# phy1.net
KiCad netlist of a schematic drawn in Altium Designer
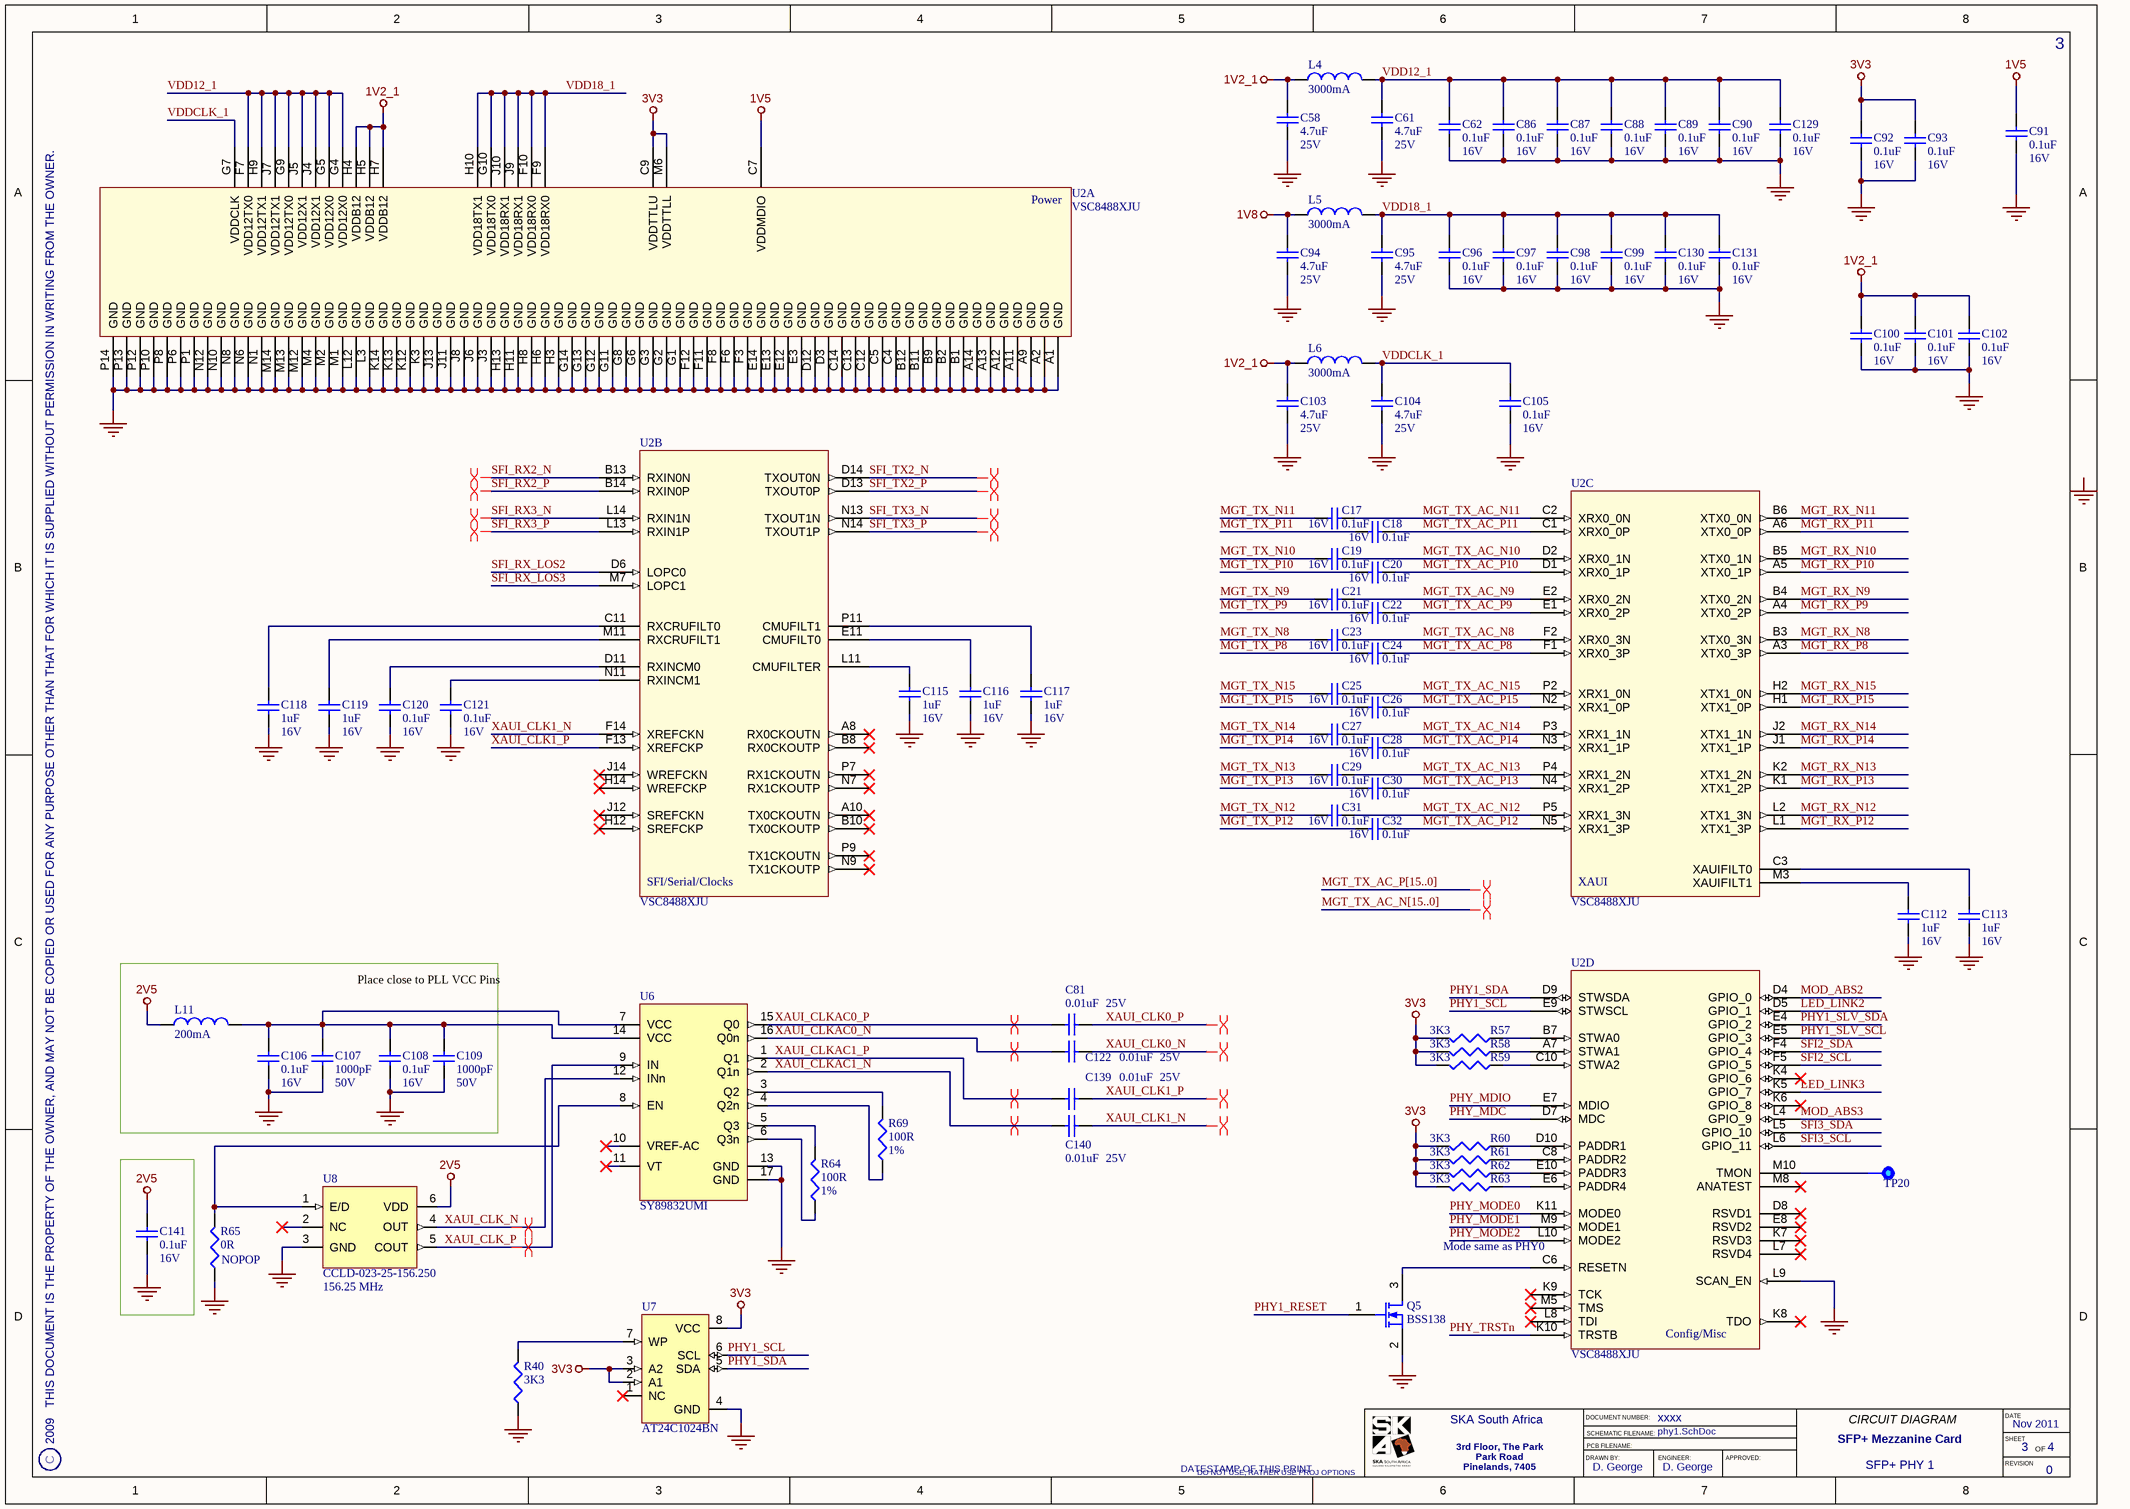
[diagram p0: phy1.SchDoc]

(export (version "E")
  (design (tool "Eeschema 10.0.6"))
  (components
    (comp (ref "C17")
      (value "0.1uF")
      (footprint "CAPC1005X60L")
      (description "0.1uF, Ceramic Capacitor")
      (fields
        (field (name "RATING") "16V")
        (field (name "MANUFACTURER") "VENKEL")
        (field (name "PARTNUM") "C0402X7R160-104KN")
      )
      (libsource (lib "altium_db") (part "CapStd"))
    )
    (comp (ref "C18")
      (value "0.1uF")
      (footprint "CAPC1005X60L")
      (description "0.1uF, Ceramic Capacitor")
      (fields
        (field (name "RATING") "16V")
        (field (name "MANUFACTURER") "VENKEL")
        (field (name "PARTNUM") "C0402X7R160-104KN")
      )
      (libsource (lib "altium_db") (part "CapStd"))
    )
    (comp (ref "C19")
      (value "0.1uF")
      (footprint "CAPC1005X60L")
      (description "0.1uF, Ceramic Capacitor")
      (fields
        (field (name "RATING") "16V")
        (field (name "MANUFACTURER") "VENKEL")
        (field (name "PARTNUM") "C0402X7R160-104KN")
      )
      (libsource (lib "altium_db") (part "CapStd"))
    )
    (comp (ref "C20")
      (value "0.1uF")
      (footprint "CAPC1005X60L")
      (description "0.1uF, Ceramic Capacitor")
      (fields
        (field (name "RATING") "16V")
        (field (name "MANUFACTURER") "VENKEL")
        (field (name "PARTNUM") "C0402X7R160-104KN")
      )
      (libsource (lib "altium_db") (part "CapStd"))
    )
    (comp (ref "C21")
      (value "0.1uF")
      (footprint "CAPC1005X60L")
      (description "0.1uF, Ceramic Capacitor")
      (fields
        (field (name "RATING") "16V")
        (field (name "MANUFACTURER") "VENKEL")
        (field (name "PARTNUM") "C0402X7R160-104KN")
      )
      (libsource (lib "altium_db") (part "CapStd"))
    )
    (comp (ref "C22")
      (value "0.1uF")
      (footprint "CAPC1005X60L")
      (description "0.1uF, Ceramic Capacitor")
      (fields
        (field (name "RATING") "16V")
        (field (name "MANUFACTURER") "VENKEL")
        (field (name "PARTNUM") "C0402X7R160-104KN")
      )
      (libsource (lib "altium_db") (part "CapStd"))
    )
    (comp (ref "C23")
      (value "0.1uF")
      (footprint "CAPC1005X60L")
      (description "0.1uF, Ceramic Capacitor")
      (fields
        (field (name "RATING") "16V")
        (field (name "MANUFACTURER") "VENKEL")
        (field (name "PARTNUM") "C0402X7R160-104KN")
      )
      (libsource (lib "altium_db") (part "CapStd"))
    )
    (comp (ref "C24")
      (value "0.1uF")
      (footprint "CAPC1005X60L")
      (description "0.1uF, Ceramic Capacitor")
      (fields
        (field (name "RATING") "16V")
        (field (name "MANUFACTURER") "VENKEL")
        (field (name "PARTNUM") "C0402X7R160-104KN")
      )
      (libsource (lib "altium_db") (part "CapStd"))
    )
    (comp (ref "C25")
      (value "0.1uF")
      (footprint "CAPC1005X60L")
      (description "0.1uF, Ceramic Capacitor")
      (fields
        (field (name "RATING") "16V")
        (field (name "MANUFACTURER") "VENKEL")
        (field (name "PARTNUM") "C0402X7R160-104KN")
      )
      (libsource (lib "altium_db") (part "CapStd"))
    )
    (comp (ref "C26")
      (value "0.1uF")
      (footprint "CAPC1005X60L")
      (description "0.1uF, Ceramic Capacitor")
      (fields
        (field (name "RATING") "16V")
        (field (name "MANUFACTURER") "VENKEL")
        (field (name "PARTNUM") "C0402X7R160-104KN")
      )
      (libsource (lib "altium_db") (part "CapStd"))
    )
    (comp (ref "C27")
      (value "0.1uF")
      (footprint "CAPC1005X60L")
      (description "0.1uF, Ceramic Capacitor")
      (fields
        (field (name "RATING") "16V")
        (field (name "MANUFACTURER") "VENKEL")
        (field (name "PARTNUM") "C0402X7R160-104KN")
      )
      (libsource (lib "altium_db") (part "CapStd"))
    )
    (comp (ref "C28")
      (value "0.1uF")
      (footprint "CAPC1005X60L")
      (description "0.1uF, Ceramic Capacitor")
      (fields
        (field (name "RATING") "16V")
        (field (name "MANUFACTURER") "VENKEL")
        (field (name "PARTNUM") "C0402X7R160-104KN")
      )
      (libsource (lib "altium_db") (part "CapStd"))
    )
    (comp (ref "C29")
      (value "0.1uF")
      (footprint "CAPC1005X60L")
      (description "0.1uF, Ceramic Capacitor")
      (fields
        (field (name "RATING") "16V")
        (field (name "MANUFACTURER") "VENKEL")
        (field (name "PARTNUM") "C0402X7R160-104KN")
      )
      (libsource (lib "altium_db") (part "CapStd"))
    )
    (comp (ref "C30")
      (value "0.1uF")
      (footprint "CAPC1005X60L")
      (description "0.1uF, Ceramic Capacitor")
      (fields
        (field (name "RATING") "16V")
        (field (name "MANUFACTURER") "VENKEL")
        (field (name "PARTNUM") "C0402X7R160-104KN")
      )
      (libsource (lib "altium_db") (part "CapStd"))
    )
    (comp (ref "C31")
      (value "0.1uF")
      (footprint "CAPC1005X60L")
      (description "0.1uF, Ceramic Capacitor")
      (fields
        (field (name "RATING") "16V")
        (field (name "MANUFACTURER") "VENKEL")
        (field (name "PARTNUM") "C0402X7R160-104KN")
      )
      (libsource (lib "altium_db") (part "CapStd"))
    )
    (comp (ref "C32")
      (value "0.1uF")
      (footprint "CAPC1005X60L")
      (description "0.1uF, Ceramic Capacitor")
      (fields
        (field (name "RATING") "16V")
        (field (name "MANUFACTURER") "VENKEL")
        (field (name "PARTNUM") "C0402X7R160-104KN")
      )
      (libsource (lib "altium_db") (part "CapStd"))
    )
    (comp (ref "C58")
      (value "4.7uF")
      (footprint "CAPC2012X127L")
      (description "4.7uF, Ceramic Capacitor")
      (fields
        (field (name "RATING") "25V")
        (field (name "MANUFACTURER") "MURATA")
        (field (name "PARTNUM") "GRM21BR61E475KA12K")
      )
      (libsource (lib "altium_db") (part "CapStd"))
    )
    (comp (ref "C61")
      (value "4.7uF")
      (footprint "CAPC2012X127L")
      (description "4.7uF, Ceramic Capacitor")
      (fields
        (field (name "RATING") "25V")
        (field (name "MANUFACTURER") "MURATA")
        (field (name "PARTNUM") "GRM21BR61E475KA12K")
      )
      (libsource (lib "altium_db") (part "CapStd"))
    )
    (comp (ref "C62")
      (value "0.1uF")
      (footprint "CAPC1005X60L")
      (description "0.1uF, Ceramic Capacitor")
      (fields
        (field (name "RATING") "16V")
        (field (name "MANUFACTURER") "VENKEL")
        (field (name "PARTNUM") "C0402X7R160-104KN")
      )
      (libsource (lib "altium_db") (part "CapStd"))
    )
    (comp (ref "C81")
      (value "0.01uF")
      (footprint "CAPC1005X55L")
      (description "0.01uF, Ceramic Capacitor")
      (fields
        (field (name "RATING") "25V")
        (field (name "MANUFACTURER") "MURATA")
        (field (name "PARTNUM") "GRM155R71E103KA01D")
      )
      (libsource (lib "altium_db") (part "CapStd"))
    )
    (comp (ref "C86")
      (value "0.1uF")
      (footprint "CAPC1005X60L")
      (description "0.1uF, Ceramic Capacitor")
      (fields
        (field (name "RATING") "16V")
        (field (name "MANUFACTURER") "VENKEL")
        (field (name "PARTNUM") "C0402X7R160-104KN")
      )
      (libsource (lib "altium_db") (part "CapStd"))
    )
    (comp (ref "C87")
      (value "0.1uF")
      (footprint "CAPC1005X60L")
      (description "0.1uF, Ceramic Capacitor")
      (fields
        (field (name "RATING") "16V")
        (field (name "MANUFACTURER") "VENKEL")
        (field (name "PARTNUM") "C0402X7R160-104KN")
      )
      (libsource (lib "altium_db") (part "CapStd"))
    )
    (comp (ref "C88")
      (value "0.1uF")
      (footprint "CAPC1005X60L")
      (description "0.1uF, Ceramic Capacitor")
      (fields
        (field (name "RATING") "16V")
        (field (name "MANUFACTURER") "VENKEL")
        (field (name "PARTNUM") "C0402X7R160-104KN")
      )
      (libsource (lib "altium_db") (part "CapStd"))
    )
    (comp (ref "C89")
      (value "0.1uF")
      (footprint "CAPC1005X60L")
      (description "0.1uF, Ceramic Capacitor")
      (fields
        (field (name "RATING") "16V")
        (field (name "MANUFACTURER") "VENKEL")
        (field (name "PARTNUM") "C0402X7R160-104KN")
      )
      (libsource (lib "altium_db") (part "CapStd"))
    )
    (comp (ref "C90")
      (value "0.1uF")
      (footprint "CAPC1005X60L")
      (description "0.1uF, Ceramic Capacitor")
      (fields
        (field (name "RATING") "16V")
        (field (name "MANUFACTURER") "VENKEL")
        (field (name "PARTNUM") "C0402X7R160-104KN")
      )
      (libsource (lib "altium_db") (part "CapStd"))
    )
    (comp (ref "C91")
      (value "0.1uF")
      (footprint "CAPC1005X60L")
      (description "0.1uF, Ceramic Capacitor")
      (fields
        (field (name "RATING") "16V")
        (field (name "MANUFACTURER") "VENKEL")
        (field (name "PARTNUM") "C0402X7R160-104KN")
      )
      (libsource (lib "altium_db") (part "CapStd"))
    )
    (comp (ref "C92")
      (value "0.1uF")
      (footprint "CAPC1005X60L")
      (description "0.1uF, Ceramic Capacitor")
      (fields
        (field (name "RATING") "16V")
        (field (name "MANUFACTURER") "VENKEL")
        (field (name "PARTNUM") "C0402X7R160-104KN")
      )
      (libsource (lib "altium_db") (part "CapStd"))
    )
    (comp (ref "C93")
      (value "0.1uF")
      (footprint "CAPC1005X60L")
      (description "0.1uF, Ceramic Capacitor")
      (fields
        (field (name "RATING") "16V")
        (field (name "MANUFACTURER") "VENKEL")
        (field (name "PARTNUM") "C0402X7R160-104KN")
      )
      (libsource (lib "altium_db") (part "CapStd"))
    )
    (comp (ref "C94")
      (value "4.7uF")
      (footprint "CAPC2012X127L")
      (description "4.7uF, Ceramic Capacitor")
      (fields
        (field (name "RATING") "25V")
        (field (name "MANUFACTURER") "MURATA")
        (field (name "PARTNUM") "GRM21BR61E475KA12K")
      )
      (libsource (lib "altium_db") (part "CapStd"))
    )
    (comp (ref "C95")
      (value "4.7uF")
      (footprint "CAPC2012X127L")
      (description "4.7uF, Ceramic Capacitor")
      (fields
        (field (name "RATING") "25V")
        (field (name "MANUFACTURER") "MURATA")
        (field (name "PARTNUM") "GRM21BR61E475KA12K")
      )
      (libsource (lib "altium_db") (part "CapStd"))
    )
    (comp (ref "C96")
      (value "0.1uF")
      (footprint "CAPC1005X60L")
      (description "0.1uF, Ceramic Capacitor")
      (fields
        (field (name "RATING") "16V")
        (field (name "MANUFACTURER") "VENKEL")
        (field (name "PARTNUM") "C0402X7R160-104KN")
      )
      (libsource (lib "altium_db") (part "CapStd"))
    )
    (comp (ref "C97")
      (value "0.1uF")
      (footprint "CAPC1005X60L")
      (description "0.1uF, Ceramic Capacitor")
      (fields
        (field (name "RATING") "16V")
        (field (name "MANUFACTURER") "VENKEL")
        (field (name "PARTNUM") "C0402X7R160-104KN")
      )
      (libsource (lib "altium_db") (part "CapStd"))
    )
    (comp (ref "C98")
      (value "0.1uF")
      (footprint "CAPC1005X60L")
      (description "0.1uF, Ceramic Capacitor")
      (fields
        (field (name "RATING") "16V")
        (field (name "MANUFACTURER") "VENKEL")
        (field (name "PARTNUM") "C0402X7R160-104KN")
      )
      (libsource (lib "altium_db") (part "CapStd"))
    )
    (comp (ref "C99")
      (value "0.1uF")
      (footprint "CAPC1005X60L")
      (description "0.1uF, Ceramic Capacitor")
      (fields
        (field (name "RATING") "16V")
        (field (name "MANUFACTURER") "VENKEL")
        (field (name "PARTNUM") "C0402X7R160-104KN")
      )
      (libsource (lib "altium_db") (part "CapStd"))
    )
    (comp (ref "C100")
      (value "0.1uF")
      (footprint "CAPC1005X60L")
      (description "0.1uF, Ceramic Capacitor")
      (fields
        (field (name "RATING") "16V")
        (field (name "MANUFACTURER") "VENKEL")
        (field (name "PARTNUM") "C0402X7R160-104KN")
      )
      (libsource (lib "altium_db") (part "CapStd"))
    )
    (comp (ref "C101")
      (value "0.1uF")
      (footprint "CAPC1005X60L")
      (description "0.1uF, Ceramic Capacitor")
      (fields
        (field (name "RATING") "16V")
        (field (name "MANUFACTURER") "VENKEL")
        (field (name "PARTNUM") "C0402X7R160-104KN")
      )
      (libsource (lib "altium_db") (part "CapStd"))
    )
    (comp (ref "C102")
      (value "0.1uF")
      (footprint "CAPC1005X60L")
      (description "0.1uF, Ceramic Capacitor")
      (fields
        (field (name "RATING") "16V")
        (field (name "MANUFACTURER") "VENKEL")
        (field (name "PARTNUM") "C0402X7R160-104KN")
      )
      (libsource (lib "altium_db") (part "CapStd"))
    )
    (comp (ref "C103")
      (value "4.7uF")
      (footprint "CAPC2012X127L")
      (description "4.7uF, Ceramic Capacitor")
      (fields
        (field (name "RATING") "25V")
        (field (name "MANUFACTURER") "MURATA")
        (field (name "PARTNUM") "GRM21BR61E475KA12K")
      )
      (libsource (lib "altium_db") (part "CapStd"))
    )
    (comp (ref "C104")
      (value "4.7uF")
      (footprint "CAPC2012X127L")
      (description "4.7uF, Ceramic Capacitor")
      (fields
        (field (name "RATING") "25V")
        (field (name "MANUFACTURER") "MURATA")
        (field (name "PARTNUM") "GRM21BR61E475KA12K")
      )
      (libsource (lib "altium_db") (part "CapStd"))
    )
    (comp (ref "C105")
      (value "0.1uF")
      (footprint "CAPC1005X60L")
      (description "0.1uF, Ceramic Capacitor")
      (fields
        (field (name "RATING") "16V")
        (field (name "MANUFACTURER") "VENKEL")
        (field (name "PARTNUM") "C0402X7R160-104KN")
      )
      (libsource (lib "altium_db") (part "CapStd"))
    )
    (comp (ref "C106")
      (value "0.1uF")
      (footprint "CAPC1005X60L")
      (description "0.1uF, Ceramic Capacitor")
      (fields
        (field (name "RATING") "16V")
        (field (name "MANUFACTURER") "VENKEL")
        (field (name "PARTNUM") "C0402X7R160-104KN")
      )
      (libsource (lib "altium_db") (part "CapStd"))
    )
    (comp (ref "C107")
      (value "1000pF")
      (footprint "CAPC1005X55L")
      (description "1000pF, Ceramic Capacitor")
      (fields
        (field (name "RATING") "50V")
        (field (name "MANUFACTURER") "MURATA")
        (field (name "PARTNUM") "GRM155R61H102KA01D")
      )
      (libsource (lib "altium_db") (part "CapStd"))
    )
    (comp (ref "C108")
      (value "0.1uF")
      (footprint "CAPC1005X60L")
      (description "0.1uF, Ceramic Capacitor")
      (fields
        (field (name "RATING") "16V")
        (field (name "MANUFACTURER") "VENKEL")
        (field (name "PARTNUM") "C0402X7R160-104KN")
      )
      (libsource (lib "altium_db") (part "CapStd"))
    )
    (comp (ref "C109")
      (value "1000pF")
      (footprint "CAPC1005X55L")
      (description "1000pF, Ceramic Capacitor")
      (fields
        (field (name "RATING") "50V")
        (field (name "MANUFACTURER") "MURATA")
        (field (name "PARTNUM") "GRM155R61H102KA01D")
      )
      (libsource (lib "altium_db") (part "CapStd"))
    )
    (comp (ref "C112")
      (value "1uF")
      (footprint "CAPC2012X127L")
      (description "1uF, Ceramic Capacitor")
      (fields
        (field (name "RATING") "16V")
        (field (name "MANUFACTURER") "MURATA")
        (field (name "PARTNUM") "GRM21BR61C105KA01L")
      )
      (libsource (lib "altium_db") (part "CapStd"))
    )
    (comp (ref "C113")
      (value "1uF")
      (footprint "CAPC2012X127L")
      (description "1uF, Ceramic Capacitor")
      (fields
        (field (name "RATING") "16V")
        (field (name "MANUFACTURER") "MURATA")
        (field (name "PARTNUM") "GRM21BR61C105KA01L")
      )
      (libsource (lib "altium_db") (part "CapStd"))
    )
    (comp (ref "C115")
      (value "1uF")
      (footprint "CAPC2012X127L")
      (description "1uF, Ceramic Capacitor")
      (fields
        (field (name "RATING") "16V")
        (field (name "MANUFACTURER") "MURATA")
        (field (name "PARTNUM") "GRM21BR61C105KA01L")
      )
      (libsource (lib "altium_db") (part "CapStd"))
    )
    (comp (ref "C116")
      (value "1uF")
      (footprint "CAPC2012X127L")
      (description "1uF, Ceramic Capacitor")
      (fields
        (field (name "RATING") "16V")
        (field (name "MANUFACTURER") "MURATA")
        (field (name "PARTNUM") "GRM21BR61C105KA01L")
      )
      (libsource (lib "altium_db") (part "CapStd"))
    )
    (comp (ref "C117")
      (value "1uF")
      (footprint "CAPC2012X127L")
      (description "1uF, Ceramic Capacitor")
      (fields
        (field (name "RATING") "16V")
        (field (name "MANUFACTURER") "MURATA")
        (field (name "PARTNUM") "GRM21BR61C105KA01L")
      )
      (libsource (lib "altium_db") (part "CapStd"))
    )
    (comp (ref "C118")
      (value "1uF")
      (footprint "CAPC2012X127L")
      (description "1uF, Ceramic Capacitor")
      (fields
        (field (name "RATING") "16V")
        (field (name "MANUFACTURER") "MURATA")
        (field (name "PARTNUM") "GRM21BR61C105KA01L")
      )
      (libsource (lib "altium_db") (part "CapStd"))
    )
    (comp (ref "C119")
      (value "1uF")
      (footprint "CAPC2012X127L")
      (description "1uF, Ceramic Capacitor")
      (fields
        (field (name "RATING") "16V")
        (field (name "MANUFACTURER") "MURATA")
        (field (name "PARTNUM") "GRM21BR61C105KA01L")
      )
      (libsource (lib "altium_db") (part "CapStd"))
    )
    (comp (ref "C120")
      (value "0.1uF")
      (footprint "CAPC1005X60L")
      (description "0.1uF, Ceramic Capacitor")
      (fields
        (field (name "RATING") "16V")
        (field (name "MANUFACTURER") "VENKEL")
        (field (name "PARTNUM") "C0402X7R160-104KN")
      )
      (libsource (lib "altium_db") (part "CapStd"))
    )
    (comp (ref "C121")
      (value "0.1uF")
      (footprint "CAPC1005X60L")
      (description "0.1uF, Ceramic Capacitor")
      (fields
        (field (name "RATING") "16V")
        (field (name "MANUFACTURER") "VENKEL")
        (field (name "PARTNUM") "C0402X7R160-104KN")
      )
      (libsource (lib "altium_db") (part "CapStd"))
    )
    (comp (ref "C122")
      (value "0.01uF")
      (footprint "CAPC1005X55L")
      (description "0.01uF, Ceramic Capacitor")
      (fields
        (field (name "RATING") "25V")
        (field (name "MANUFACTURER") "MURATA")
        (field (name "PARTNUM") "GRM155R71E103KA01D")
      )
      (libsource (lib "altium_db") (part "CapStd"))
    )
    (comp (ref "C129")
      (value "0.1uF")
      (footprint "CAPC1005X60L")
      (description "0.1uF, Ceramic Capacitor")
      (fields
        (field (name "RATING") "16V")
        (field (name "MANUFACTURER") "VENKEL")
        (field (name "PARTNUM") "C0402X7R160-104KN")
      )
      (libsource (lib "altium_db") (part "CapStd"))
    )
    (comp (ref "C130")
      (value "0.1uF")
      (footprint "CAPC1005X60L")
      (description "0.1uF, Ceramic Capacitor")
      (fields
        (field (name "RATING") "16V")
        (field (name "MANUFACTURER") "VENKEL")
        (field (name "PARTNUM") "C0402X7R160-104KN")
      )
      (libsource (lib "altium_db") (part "CapStd"))
    )
    (comp (ref "C131")
      (value "0.1uF")
      (footprint "CAPC1005X60L")
      (description "0.1uF, Ceramic Capacitor")
      (fields
        (field (name "RATING") "16V")
        (field (name "MANUFACTURER") "VENKEL")
        (field (name "PARTNUM") "C0402X7R160-104KN")
      )
      (libsource (lib "altium_db") (part "CapStd"))
    )
    (comp (ref "C139")
      (value "0.01uF")
      (footprint "CAPC1005X55L")
      (description "0.01uF, Ceramic Capacitor")
      (fields
        (field (name "RATING") "25V")
        (field (name "MANUFACTURER") "MURATA")
        (field (name "PARTNUM") "GRM155R71E103KA01D")
      )
      (libsource (lib "altium_db") (part "CapStd"))
    )
    (comp (ref "C140")
      (value "0.01uF")
      (footprint "CAPC1005X55L")
      (description "0.01uF, Ceramic Capacitor")
      (fields
        (field (name "RATING") "25V")
        (field (name "MANUFACTURER") "MURATA")
        (field (name "PARTNUM") "GRM155R71E103KA01D")
      )
      (libsource (lib "altium_db") (part "CapStd"))
    )
    (comp (ref "C141")
      (value "0.1uF")
      (footprint "CAPC1005X60L")
      (description "0.1uF, Ceramic Capacitor")
      (fields
        (field (name "RATING") "16V")
        (field (name "MANUFACTURER") "VENKEL")
        (field (name "PARTNUM") "C0402X7R160-104KN")
      )
      (libsource (lib "altium_db") (part "CapStd"))
    )
    (comp (ref "L4")
      (value "120R")
      (footprint "INDC3216X130L")
      (description "120 Ohm, Chip Ferrite Brad")
      (fields
        (field (name "RATING") "3000mA")
        (field (name "MANUFACTURER") "Murata")
        (field (name "PARTNUM") "BLM31PG121SN1")
      )
      (libsource (lib "altium_db") (part "IndStd"))
    )
    (comp (ref "L5")
      (value "120R")
      (footprint "INDC3216X130L")
      (description "120 Ohm, Chip Ferrite Brad")
      (fields
        (field (name "RATING") "3000mA")
        (field (name "MANUFACTURER") "Murata")
        (field (name "PARTNUM") "BLM31PG121SN1")
      )
      (libsource (lib "altium_db") (part "IndStd"))
    )
    (comp (ref "L6")
      (value "120R")
      (footprint "INDC3216X130L")
      (description "120 Ohm, Chip Ferrite Brad")
      (fields
        (field (name "RATING") "3000mA")
        (field (name "MANUFACTURER") "Murata")
        (field (name "PARTNUM") "BLM31PG121SN1")
      )
      (libsource (lib "altium_db") (part "IndStd"))
    )
    (comp (ref "L11")
      (value "600R")
      (footprint "INDC2012X130L")
      (description "600 Ohm, Chip Ferrite Bead")
      (fields
        (field (name "RATING") "200mA")
        (field (name "MANUFACTURER") "Murata")
        (field (name "PARTNUM") "BLM21BD601SN1")
      )
      (libsource (lib "altium_db") (part "IndStd"))
    )
    (comp (ref "Q5")
      (value "BSS138")
      (footprint "SOT95P245X110-3N")
      (description "N-Channel Logic Level Enhancement Mode Field Effect Transistor")
      (fields (field (name "MANUFACTURER") "Fairchild Semiconductor"))
      (libsource (lib "altium_db") (part "BSS138"))
    )
    (comp (ref "R40")
      (value "3K3")
      (footprint "RESC1005X40L")
      (description "3K3, 1.1mm x 0.5mm, Thick Film Resistor")
      (fields (field (name "MANUFACTURER") "ROYALOHM") (field (name "PARTNUM") "0402WGJ0332T1E"))
      (libsource (lib "altium_db") (part "ResStd"))
    )
    (comp (ref "R57")
      (value "3K3")
      (footprint "RESC1005X40L")
      (description "3K3, 1.1mm x 0.5mm, Thick Film Resistor")
      (fields (field (name "MANUFACTURER") "ROYALOHM") (field (name "PARTNUM") "0402WGJ0332T1E"))
      (libsource (lib "altium_db") (part "ResStd"))
    )
    (comp (ref "R58")
      (value "3K3")
      (footprint "RESC1005X40L")
      (description "3K3, 1.1mm x 0.5mm, Thick Film Resistor")
      (fields (field (name "MANUFACTURER") "ROYALOHM") (field (name "PARTNUM") "0402WGJ0332T1E"))
      (libsource (lib "altium_db") (part "ResStd"))
    )
    (comp (ref "R59")
      (value "3K3")
      (footprint "RESC1005X40L")
      (description "3K3, 1.1mm x 0.5mm, Thick Film Resistor")
      (fields (field (name "MANUFACTURER") "ROYALOHM") (field (name "PARTNUM") "0402WGJ0332T1E"))
      (libsource (lib "altium_db") (part "ResStd"))
    )
    (comp (ref "R60")
      (value "3K3")
      (footprint "RESC1005X40L")
      (description "3K3, 1.1mm x 0.5mm, Thick Film Resistor")
      (fields (field (name "MANUFACTURER") "ROYALOHM") (field (name "PARTNUM") "0402WGJ0332T1E"))
      (libsource (lib "altium_db") (part "ResStd"))
    )
    (comp (ref "R61")
      (value "3K3")
      (footprint "RESC1005X40L")
      (description "3K3, 1.1mm x 0.5mm, Thick Film Resistor")
      (fields (field (name "MANUFACTURER") "ROYALOHM") (field (name "PARTNUM") "0402WGJ0332T1E"))
      (libsource (lib "altium_db") (part "ResStd"))
    )
    (comp (ref "R62")
      (value "3K3")
      (footprint "RESC1005X40L")
      (description "3K3, 1.1mm x 0.5mm, Thick Film Resistor")
      (fields (field (name "MANUFACTURER") "ROYALOHM") (field (name "PARTNUM") "0402WGJ0332T1E"))
      (libsource (lib "altium_db") (part "ResStd"))
    )
    (comp (ref "R63")
      (value "3K3")
      (footprint "RESC1005X40L")
      (description "3K3, 1.1mm x 0.5mm, Thick Film Resistor")
      (fields (field (name "MANUFACTURER") "ROYALOHM") (field (name "PARTNUM") "0402WGJ0332T1E"))
      (libsource (lib "altium_db") (part "ResStd"))
    )
    (comp (ref "R64")
      (value "100R")
      (footprint "RESC1005X40L")
      (description "100R, 1.1mm x 0.5mm, Thick Film Resistor")
      (fields
        (field (name "MANUFACTURER") "ROYALOHM")
        (field (name "PARTNUM") "0402WGF0101T1E")
        (field (name "TOLERANCE") "1%")
      )
      (libsource (lib "altium_db") (part "ResStd"))
    )
    (comp (ref "R65")
      (value "0R")
      (footprint "RESC1005X40L")
      (description "0R, 1.1mm x 0.5mm, Thick Film Resistor")
      (fields (field (name "MANUFACTURER") "ROYALOHM") (field (name "PARTNUM") "0402WG00000T1E"))
      (libsource (lib "altium_db") (part "ResStd"))
    )
    (comp (ref "R69")
      (value "100R")
      (footprint "RESC1005X40L")
      (description "100R, 1.1mm x 0.5mm, Thick Film Resistor")
      (fields
        (field (name "MANUFACTURER") "ROYALOHM")
        (field (name "PARTNUM") "0402WGF0101T1E")
        (field (name "TOLERANCE") "1%")
      )
      (libsource (lib "altium_db") (part "ResStd"))
    )
    (comp (ref "TP20")
      (value "Testpoint")
      (footprint "TP100")
      (description "1mm Diameter, through-hole, Circular Test-point")
      (libsource (lib "altium_db") (part "Testpoint"))
    )
    (comp (ref "U2")
      (value "VSC8488XJU")
      (footprint "BGA196C100P14X14_1500x1500x140")
      (description "DualChannel WAN/LAN/Backplane XAUI to SFP+/KR Transceiver")
      (fields (field (name "MANUFACTURER") "Vitesse"))
      (libsource (lib "altium_db") (part "VSC8488XJU"))
    )
    (comp (ref "U6")
      (value "SY89832UMI")
      (footprint "MLF-16")
      (description "2.5 C Ultra-precision 1:4 LVDS Fanout Buffer/Translator with Interal Termination")
      (fields (field (name "MANUFACTURER") "Micrel"))
      (libsource (lib "altium_db") (part "SY89832UMI"))
    )
    (comp (ref "U7")
      (value "AT24C1024BN")
      (footprint "SOIC150-8_N")
      (description "1M, SOIC-8, Serial EEPROM")
      (fields (field (name "MANUFACTURER") "Atmel") (field (name "PARTNUM") "AT24C1024BN-SH-B"))
      (libsource (lib "altium_db") (part "AT24C1024BN-SH"))
    )
    (comp (ref "U8")
      (value "CCLD-023-25-156.250")
      (footprint "CCLD-023X-XX-XXX_XXX")
      (description "156.25 MHz, Low-Jitter Differential LVDS Clock Oscillator")
      (fields
        (field (name "PARTNUM") "CCLD-023-25-156.250")
        (field (name "FREQUENCY") "156.25 MHz")
        (field (name "MANUFACTURER") "Crystek")
      )
      (libsource (lib "altium_db") (part "CCLD-023X-XX-XXX_XXX"))
    )
  )
  (nets
    (net (code "17") (name "/LED_LINK2") (class "Default")
      (node (ref "U2") (pin "D5") (pinfunction "GPIO_1_D5") (pintype "bidirectional"))
    )
    (net (code "18") (name "/LED_LINK3") (class "Default")
      (node (ref "U2") (pin "K5") (pinfunction "GPIO_7_K5") (pintype "bidirectional"))
    )
    (net (code "19") (name "/MGT_RX_N8") (class "Default")
      (node (ref "U2") (pin "B3") (pinfunction "XTX0_3N_B3") (pintype "output"))
    )
    (net (code "20") (name "/MGT_RX_N9") (class "Default")
      (node (ref "U2") (pin "B4") (pinfunction "XTX0_2N_B4") (pintype "output"))
    )
    (net (code "21") (name "/MGT_RX_N10") (class "Default")
      (node (ref "U2") (pin "B5") (pinfunction "XTX0_1N_B5") (pintype "output"))
    )
    (net (code "22") (name "/MGT_RX_N11") (class "Default")
      (node (ref "U2") (pin "B6") (pinfunction "XTX0_0N_B6") (pintype "output"))
    )
    (net (code "23") (name "/MGT_RX_N12") (class "Default")
      (node (ref "U2") (pin "L2") (pinfunction "XTX1_3N_L2") (pintype "output"))
    )
    (net (code "24") (name "/MGT_RX_N13") (class "Default")
      (node (ref "U2") (pin "K2") (pinfunction "XTX1_2N_K2") (pintype "output"))
    )
    (net (code "25") (name "/MGT_RX_N14") (class "Default")
      (node (ref "U2") (pin "J2") (pinfunction "XTX1_1N_J2") (pintype "output"))
    )
    (net (code "26") (name "/MGT_RX_N15") (class "Default")
      (node (ref "U2") (pin "H2") (pinfunction "XTX1_0N_H2") (pintype "output"))
    )
    (net (code "27") (name "/MGT_RX_P8") (class "Default")
      (node (ref "U2") (pin "A3") (pinfunction "XTX0_3P_A3") (pintype "output"))
    )
    (net (code "28") (name "/MGT_RX_P9") (class "Default")
      (node (ref "U2") (pin "A4") (pinfunction "XTX0_2P_A4") (pintype "output"))
    )
    (net (code "29") (name "/MGT_RX_P10") (class "Default")
      (node (ref "U2") (pin "A5") (pinfunction "XTX0_1P_A5") (pintype "output"))
    )
    (net (code "30") (name "/MGT_RX_P11") (class "Default")
      (node (ref "U2") (pin "A6") (pinfunction "XTX0_0P_A6") (pintype "output"))
    )
    (net (code "31") (name "/MGT_RX_P12") (class "Default")
      (node (ref "U2") (pin "L1") (pinfunction "XTX1_3P_L1") (pintype "output"))
    )
    (net (code "32") (name "/MGT_RX_P13") (class "Default")
      (node (ref "U2") (pin "K1") (pinfunction "XTX1_2P_K1") (pintype "output"))
    )
    (net (code "33") (name "/MGT_RX_P14") (class "Default")
      (node (ref "U2") (pin "J1") (pinfunction "XTX1_1P_J1") (pintype "output"))
    )
    (net (code "34") (name "/MGT_RX_P15") (class "Default")
      (node (ref "U2") (pin "H1") (pinfunction "XTX1_0P_H1") (pintype "output"))
    )
    (net (code "35") (name "/MGT_TX_AC_N8") (class "Default")
      (node (ref "C23") (pin "1") (pinfunction "1_1") (pintype "passive"))
      (node (ref "U2") (pin "F2") (pinfunction "XRX0_3N_F2") (pintype "input"))
    )
    (net (code "36") (name "/MGT_TX_AC_N9") (class "Default")
      (node (ref "C21") (pin "1") (pinfunction "1_1") (pintype "passive"))
      (node (ref "U2") (pin "E2") (pinfunction "XRX0_2N_E2") (pintype "input"))
    )
    (net (code "37") (name "/MGT_TX_AC_N10") (class "Default")
      (node (ref "C19") (pin "1") (pinfunction "1_1") (pintype "passive"))
      (node (ref "U2") (pin "D2") (pinfunction "XRX0_1N_D2") (pintype "input"))
    )
    (net (code "38") (name "/MGT_TX_AC_N11") (class "Default")
      (node (ref "C17") (pin "1") (pinfunction "1_1") (pintype "passive"))
      (node (ref "U2") (pin "C2") (pinfunction "XRX0_0N_C2") (pintype "input"))
    )
    (net (code "39") (name "/MGT_TX_AC_N12") (class "Default")
      (node (ref "C31") (pin "1") (pinfunction "1_1") (pintype "passive"))
      (node (ref "U2") (pin "P5") (pinfunction "XRX1_3N_P5") (pintype "input"))
    )
    (net (code "40") (name "/MGT_TX_AC_N13") (class "Default")
      (node (ref "C29") (pin "1") (pinfunction "1_1") (pintype "passive"))
      (node (ref "U2") (pin "P4") (pinfunction "XRX1_2N_P4") (pintype "input"))
    )
    (net (code "41") (name "/MGT_TX_AC_N14") (class "Default")
      (node (ref "C27") (pin "1") (pinfunction "1_1") (pintype "passive"))
      (node (ref "U2") (pin "P3") (pinfunction "XRX1_1N_P3") (pintype "input"))
    )
    (net (code "42") (name "/MGT_TX_AC_N15") (class "Default")
      (node (ref "C25") (pin "1") (pinfunction "1_1") (pintype "passive"))
      (node (ref "U2") (pin "P2") (pinfunction "XRX1_0N_P2") (pintype "input"))
    )
    (net (code "44") (name "/MGT_TX_AC_P8") (class "Default")
      (node (ref "C24") (pin "1") (pinfunction "1_1") (pintype "passive"))
      (node (ref "U2") (pin "F1") (pinfunction "XRX0_3P_F1") (pintype "input"))
    )
    (net (code "45") (name "/MGT_TX_AC_P9") (class "Default")
      (node (ref "C22") (pin "1") (pinfunction "1_1") (pintype "passive"))
      (node (ref "U2") (pin "E1") (pinfunction "XRX0_2P_E1") (pintype "input"))
    )
    (net (code "46") (name "/MGT_TX_AC_P10") (class "Default")
      (node (ref "C20") (pin "1") (pinfunction "1_1") (pintype "passive"))
      (node (ref "U2") (pin "D1") (pinfunction "XRX0_1P_D1") (pintype "input"))
    )
    (net (code "47") (name "/MGT_TX_AC_P11") (class "Default")
      (node (ref "C18") (pin "1") (pinfunction "1_1") (pintype "passive"))
      (node (ref "U2") (pin "C1") (pinfunction "XRX0_0P_C1") (pintype "input"))
    )
    (net (code "48") (name "/MGT_TX_AC_P12") (class "Default")
      (node (ref "C32") (pin "1") (pinfunction "1_1") (pintype "passive"))
      (node (ref "U2") (pin "N5") (pinfunction "XRX1_3P_N5") (pintype "input"))
    )
    (net (code "49") (name "/MGT_TX_AC_P13") (class "Default")
      (node (ref "C30") (pin "1") (pinfunction "1_1") (pintype "passive"))
      (node (ref "U2") (pin "N4") (pinfunction "XRX1_2P_N4") (pintype "input"))
    )
    (net (code "50") (name "/MGT_TX_AC_P14") (class "Default")
      (node (ref "C28") (pin "1") (pinfunction "1_1") (pintype "passive"))
      (node (ref "U2") (pin "N3") (pinfunction "XRX1_1P_N3") (pintype "input"))
    )
    (net (code "51") (name "/MGT_TX_AC_P15") (class "Default")
      (node (ref "C26") (pin "1") (pinfunction "1_1") (pintype "passive"))
      (node (ref "U2") (pin "N2") (pinfunction "XRX1_0P_N2") (pintype "input"))
    )
    (net (code "53") (name "/MGT_TX_N8") (class "Default")
      (node (ref "C23") (pin "2") (pinfunction "2_2") (pintype "passive"))
    )
    (net (code "54") (name "/MGT_TX_N9") (class "Default")
      (node (ref "C21") (pin "2") (pinfunction "2_2") (pintype "passive"))
    )
    (net (code "55") (name "/MGT_TX_N10") (class "Default")
      (node (ref "C19") (pin "2") (pinfunction "2_2") (pintype "passive"))
    )
    (net (code "56") (name "/MGT_TX_N11") (class "Default")
      (node (ref "C17") (pin "2") (pinfunction "2_2") (pintype "passive"))
    )
    (net (code "57") (name "/MGT_TX_N12") (class "Default")
      (node (ref "C31") (pin "2") (pinfunction "2_2") (pintype "passive"))
    )
    (net (code "58") (name "/MGT_TX_N13") (class "Default")
      (node (ref "C29") (pin "2") (pinfunction "2_2") (pintype "passive"))
    )
    (net (code "59") (name "/MGT_TX_N14") (class "Default")
      (node (ref "C27") (pin "2") (pinfunction "2_2") (pintype "passive"))
    )
    (net (code "60") (name "/MGT_TX_N15") (class "Default")
      (node (ref "C25") (pin "2") (pinfunction "2_2") (pintype "passive"))
    )
    (net (code "61") (name "/MGT_TX_P8") (class "Default")
      (node (ref "C24") (pin "2") (pinfunction "2_2") (pintype "passive"))
    )
    (net (code "62") (name "/MGT_TX_P9") (class "Default")
      (node (ref "C22") (pin "2") (pinfunction "2_2") (pintype "passive"))
    )
    (net (code "63") (name "/MGT_TX_P10") (class "Default")
      (node (ref "C20") (pin "2") (pinfunction "2_2") (pintype "passive"))
    )
    (net (code "64") (name "/MGT_TX_P11") (class "Default")
      (node (ref "C18") (pin "2") (pinfunction "2_2") (pintype "passive"))
    )
    (net (code "65") (name "/MGT_TX_P12") (class "Default")
      (node (ref "C32") (pin "2") (pinfunction "2_2") (pintype "passive"))
    )
    (net (code "66") (name "/MGT_TX_P13") (class "Default")
      (node (ref "C30") (pin "2") (pinfunction "2_2") (pintype "passive"))
    )
    (net (code "67") (name "/MGT_TX_P14") (class "Default")
      (node (ref "C28") (pin "2") (pinfunction "2_2") (pintype "passive"))
    )
    (net (code "68") (name "/MGT_TX_P15") (class "Default")
      (node (ref "C26") (pin "2") (pinfunction "2_2") (pintype "passive"))
    )
    (net (code "69") (name "/MOD_ABS2") (class "Default")
      (node (ref "U2") (pin "D4") (pinfunction "GPIO_0_D4") (pintype "bidirectional"))
    )
    (net (code "70") (name "/MOD_ABS3") (class "Default")
      (node (ref "U2") (pin "L4") (pinfunction "GPIO_9_L4") (pintype "bidirectional"))
    )
    (net (code "71") (name "/PHY1_RESET") (class "Default")
      (node (ref "Q5") (pin "1") (pinfunction "G_1") (pintype "passive"))
    )
    (net (code "72") (name "/PHY1_SCL") (class "Default")
      (node (ref "U2") (pin "E9") (pinfunction "STWSCL_E9") (pintype "bidirectional"))
      (node (ref "U7") (pin "6") (pinfunction "SCL_6") (pintype "bidirectional"))
    )
    (net (code "73") (name "/PHY1_SDA") (class "Default")
      (node (ref "U2") (pin "D9") (pinfunction "STWSDA_D9") (pintype "bidirectional"))
      (node (ref "U7") (pin "5") (pinfunction "SDA_5") (pintype "bidirectional"))
    )
    (net (code "74") (name "/PHY1_SLV_SCL") (class "Default")
      (node (ref "U2") (pin "E5") (pinfunction "GPIO_3_E5") (pintype "bidirectional"))
    )
    (net (code "75") (name "/PHY1_SLV_SDA") (class "Default")
      (node (ref "U2") (pin "E4") (pinfunction "GPIO_2_E4") (pintype "bidirectional"))
    )
    (net (code "76") (name "/PHY_MDC") (class "Default")
      (node (ref "U2") (pin "D7") (pinfunction "MDC_D7") (pintype "bidirectional"))
    )
    (net (code "77") (name "/PHY_MDIO") (class "Default")
      (node (ref "U2") (pin "E7") (pinfunction "MDIO_E7") (pintype "input"))
    )
    (net (code "78") (name "/PHY_MODE0") (class "Default")
      (node (ref "U2") (pin "K11") (pinfunction "MODE0_K11") (pintype "input"))
    )
    (net (code "79") (name "/PHY_MODE1") (class "Default")
      (node (ref "U2") (pin "M9") (pinfunction "MODE1_M9") (pintype "input"))
    )
    (net (code "80") (name "/PHY_MODE2") (class "Default")
      (node (ref "U2") (pin "L10") (pinfunction "MODE2_L10") (pintype "input"))
    )
    (net (code "81") (name "/PHY_TRSTn") (class "Default")
      (node (ref "U2") (pin "K10") (pinfunction "TRSTB_K10") (pintype "input"))
    )
    (net (code "82") (name "/SFI2_SCL") (class "Default")
      (node (ref "U2") (pin "F5") (pinfunction "GPIO_5_F5") (pintype "bidirectional"))
    )
    (net (code "83") (name "/SFI2_SDA") (class "Default")
      (node (ref "U2") (pin "F4") (pinfunction "GPIO_4_F4") (pintype "bidirectional"))
    )
    (net (code "84") (name "/SFI3_SCL") (class "Default")
      (node (ref "U2") (pin "L6") (pinfunction "GPIO_11_L6") (pintype "bidirectional"))
    )
    (net (code "85") (name "/SFI3_SDA") (class "Default")
      (node (ref "U2") (pin "L5") (pinfunction "GPIO_10_L5") (pintype "bidirectional"))
    )
    (net (code "86") (name "/SFI_RX2_N") (class "Default")
      (node (ref "U2") (pin "B13") (pinfunction "RXIN0N_B13") (pintype "input"))
    )
    (net (code "87") (name "/SFI_RX2_P") (class "Default")
      (node (ref "U2") (pin "B14") (pinfunction "RXIN0P_B14") (pintype "input"))
    )
    (net (code "88") (name "/SFI_RX3_N") (class "Default")
      (node (ref "U2") (pin "L14") (pinfunction "RXIN1N_L14") (pintype "input"))
    )
    (net (code "89") (name "/SFI_RX3_P") (class "Default")
      (node (ref "U2") (pin "L13") (pinfunction "RXIN1P_L13") (pintype "input"))
    )
    (net (code "90") (name "/SFI_RX_LOS2") (class "Default")
      (node (ref "U2") (pin "D6") (pinfunction "LOPC0_D6") (pintype "input"))
    )
    (net (code "91") (name "/SFI_RX_LOS3") (class "Default")
      (node (ref "U2") (pin "M7") (pinfunction "LOPC1_M7") (pintype "input"))
    )
    (net (code "92") (name "/SFI_TX2_N") (class "Default")
      (node (ref "U2") (pin "D14") (pinfunction "TXOUT0N_D14") (pintype "output"))
    )
    (net (code "93") (name "/SFI_TX2_P") (class "Default")
      (node (ref "U2") (pin "D13") (pinfunction "TXOUT0P_D13") (pintype "output"))
    )
    (net (code "94") (name "/SFI_TX3_N") (class "Default")
      (node (ref "U2") (pin "N13") (pinfunction "TXOUT1N_N13") (pintype "output"))
    )
    (net (code "95") (name "/SFI_TX3_P") (class "Default")
      (node (ref "U2") (pin "N14") (pinfunction "TXOUT1P_N14") (pintype "output"))
    )
    (net (code "96") (name "/VDD12_1") (class "Default")
      (node (ref "C129") (pin "2") (pinfunction "2_2") (pintype "passive"))
      (node (ref "C61") (pin "2") (pinfunction "2_2") (pintype "passive"))
      (node (ref "C62") (pin "2") (pinfunction "2_2") (pintype "passive"))
      (node (ref "C86") (pin "2") (pinfunction "2_2") (pintype "passive"))
      (node (ref "C87") (pin "2") (pinfunction "2_2") (pintype "passive"))
      (node (ref "C88") (pin "2") (pinfunction "2_2") (pintype "passive"))
      (node (ref "C89") (pin "2") (pinfunction "2_2") (pintype "passive"))
      (node (ref "C90") (pin "2") (pinfunction "2_2") (pintype "passive"))
      (node (ref "L4") (pin "2") (pinfunction "2_2") (pintype "passive"))
      (node (ref "U2") (pin "F7") (pinfunction "VDD12TX0_F7") (pintype "power_in"))
      (node (ref "U2") (pin "G4") (pinfunction "VDD12X0_G4") (pintype "power_in"))
      (node (ref "U2") (pin "G5") (pinfunction "VDD12X0_G5") (pintype "power_in"))
      (node (ref "U2") (pin "G9") (pinfunction "VDD12TX0_G9") (pintype "power_in"))
      (node (ref "U2") (pin "H9") (pinfunction "VDD12TX1_H9") (pintype "power_in"))
      (node (ref "U2") (pin "J4") (pinfunction "VDD12X1_J4") (pintype "power_in"))
      (node (ref "U2") (pin "J5") (pinfunction "VDD12X1_J5") (pintype "power_in"))
      (node (ref "U2") (pin "J7") (pinfunction "VDD12TX1_J7") (pintype "power_in"))
    )
    (net (code "97") (name "/VDD18_1") (class "Default")
      (node (ref "C130") (pin "2") (pinfunction "2_2") (pintype "passive"))
      (node (ref "C131") (pin "2") (pinfunction "2_2") (pintype "passive"))
      (node (ref "C95") (pin "2") (pinfunction "2_2") (pintype "passive"))
      (node (ref "C96") (pin "2") (pinfunction "2_2") (pintype "passive"))
      (node (ref "C97") (pin "2") (pinfunction "2_2") (pintype "passive"))
      (node (ref "C98") (pin "2") (pinfunction "2_2") (pintype "passive"))
      (node (ref "C99") (pin "2") (pinfunction "2_2") (pintype "passive"))
      (node (ref "L5") (pin "2") (pinfunction "2_2") (pintype "passive"))
      (node (ref "U2") (pin "F10") (pinfunction "VDD18RX0_F10") (pintype "power_in"))
      (node (ref "U2") (pin "F9") (pinfunction "VDD18RX0_F9") (pintype "power_in"))
      (node (ref "U2") (pin "G10") (pinfunction "VDD18TX0_G10") (pintype "power_in"))
      (node (ref "U2") (pin "H10") (pinfunction "VDD18TX1_H10") (pintype "power_in"))
      (node (ref "U2") (pin "J10") (pinfunction "VDD18RX1_J10") (pintype "power_in"))
      (node (ref "U2") (pin "J9") (pinfunction "VDD18RX1_J9") (pintype "power_in"))
    )
    (net (code "98") (name "/VDDCLK_1") (class "Default")
      (node (ref "C104") (pin "2") (pinfunction "2_2") (pintype "passive"))
      (node (ref "C105") (pin "2") (pinfunction "2_2") (pintype "passive"))
      (node (ref "L6") (pin "2") (pinfunction "2_2") (pintype "passive"))
      (node (ref "U2") (pin "G7") (pinfunction "VDDCLK_G7") (pintype "power_in"))
    )
    (net (code "99") (name "/XAUI_CLK0_N") (class "Default")
      (node (ref "C122") (pin "2") (pinfunction "2_2") (pintype "passive"))
    )
    (net (code "100") (name "/XAUI_CLK0_P") (class "Default")
      (node (ref "C81") (pin "2") (pinfunction "2_2") (pintype "passive"))
    )
    (net (code "101") (name "/XAUI_CLK1_N") (class "Default")
      (node (ref "C140") (pin "2") (pinfunction "2_2") (pintype "passive"))
      (node (ref "U2") (pin "F14") (pinfunction "XREFCKN_F14") (pintype "input"))
    )
    (net (code "102") (name "/XAUI_CLK1_P") (class "Default")
      (node (ref "C139") (pin "2") (pinfunction "2_2") (pintype "passive"))
      (node (ref "U2") (pin "F13") (pinfunction "XREFCKP_F13") (pintype "input"))
    )
    (net (code "103") (name "/XAUI_CLKAC0_N") (class "Default")
      (node (ref "C122") (pin "1") (pinfunction "1_1") (pintype "passive"))
      (node (ref "U6") (pin "16") (pinfunction "Q0n_16") (pintype "output"))
    )
    (net (code "104") (name "/XAUI_CLKAC0_P") (class "Default")
      (node (ref "C81") (pin "1") (pinfunction "1_1") (pintype "passive"))
      (node (ref "U6") (pin "15") (pinfunction "Q0_15") (pintype "output"))
    )
    (net (code "105") (name "/XAUI_CLKAC1_N") (class "Default")
      (node (ref "C140") (pin "1") (pinfunction "1_1") (pintype "passive"))
      (node (ref "U6") (pin "2") (pinfunction "Q1n_2") (pintype "output"))
    )
    (net (code "106") (name "/XAUI_CLKAC1_P") (class "Default")
      (node (ref "C139") (pin "1") (pinfunction "1_1") (pintype "passive"))
      (node (ref "U6") (pin "1") (pinfunction "Q1_1") (pintype "output"))
    )
    (net (code "107") (name "/XAUI_CLK_N") (class "Default")
      (node (ref "U6") (pin "12") (pinfunction "INn_12") (pintype "input"))
      (node (ref "U8") (pin "4") (pinfunction "OUT_4") (pintype "output"))
    )
    (net (code "108") (name "/XAUI_CLK_P") (class "Default")
      (node (ref "U6") (pin "9") (pinfunction "IN_9") (pintype "input"))
      (node (ref "U8") (pin "5") (pinfunction "COUT_5") (pintype "output"))
    )
    (net (code "109") (name "1V2_1") (class "Default")
      (node (ref "C100") (pin "2") (pinfunction "2_2") (pintype "passive"))
      (node (ref "C101") (pin "2") (pinfunction "2_2") (pintype "passive"))
      (node (ref "C102") (pin "2") (pinfunction "2_2") (pintype "passive"))
      (node (ref "C103") (pin "2") (pinfunction "2_2") (pintype "passive"))
      (node (ref "C58") (pin "2") (pinfunction "2_2") (pintype "passive"))
      (node (ref "L4") (pin "1") (pinfunction "1_1") (pintype "passive"))
      (node (ref "L6") (pin "1") (pinfunction "1_1") (pintype "passive"))
      (node (ref "U2") (pin "H4") (pinfunction "VDDB12_H4") (pintype "power_in"))
      (node (ref "U2") (pin "H5") (pinfunction "VDDB12_H5") (pintype "power_in"))
      (node (ref "U2") (pin "H7") (pinfunction "VDDB12_H7") (pintype "power_in"))
    )
    (net (code "110") (name "1V5") (class "Default")
      (node (ref "C91") (pin "2") (pinfunction "2_2") (pintype "passive"))
      (node (ref "U2") (pin "C7") (pinfunction "VDDMDIO_C7") (pintype "power_in"))
    )
    (net (code "111") (name "1V8") (class "Default")
      (node (ref "C94") (pin "2") (pinfunction "2_2") (pintype "passive"))
      (node (ref "L5") (pin "1") (pinfunction "1_1") (pintype "passive"))
    )
    (net (code "112") (name "2V5") (class "Default")
      (node (ref "C141") (pin "2") (pinfunction "2_2") (pintype "passive"))
      (node (ref "L11") (pin "1") (pinfunction "1_1") (pintype "passive"))
      (node (ref "U8") (pin "6") (pinfunction "VDD_6") (pintype "power_in"))
    )
    (net (code "113") (name "3V3") (class "Default")
      (node (ref "C92") (pin "2") (pinfunction "2_2") (pintype "passive"))
      (node (ref "C93") (pin "2") (pinfunction "2_2") (pintype "passive"))
      (node (ref "R57") (pin "2") (pinfunction "2_2") (pintype "passive"))
      (node (ref "R58") (pin "2") (pinfunction "2_2") (pintype "passive"))
      (node (ref "R59") (pin "2") (pinfunction "2_2") (pintype "passive"))
      (node (ref "R60") (pin "2") (pinfunction "2_2") (pintype "passive"))
      (node (ref "R61") (pin "2") (pinfunction "2_2") (pintype "passive"))
      (node (ref "R62") (pin "2") (pinfunction "2_2") (pintype "passive"))
      (node (ref "R63") (pin "2") (pinfunction "2_2") (pintype "passive"))
      (node (ref "U2") (pin "C9") (pinfunction "VDDTTLU_C9") (pintype "power_in"))
      (node (ref "U2") (pin "M6") (pinfunction "VDDTTLL_M6") (pintype "power_in"))
      (node (ref "U7") (pin "2") (pinfunction "A1_2") (pintype "input"))
      (node (ref "U7") (pin "3") (pinfunction "A2_3") (pintype "input"))
      (node (ref "U7") (pin "8") (pinfunction "VCC_8") (pintype "passive"))
    )
    (net (code "114") (name "<NO NET>") (class "Default")
      (node (ref "C103") (pin "1") (pinfunction "1_1") (pintype "passive"))
    )
    (net (code "115") (name "GND") (class "Default")
      (node (ref "C100") (pin "1") (pinfunction "1_1") (pintype "passive"))
      (node (ref "C101") (pin "1") (pinfunction "1_1") (pintype "passive"))
      (node (ref "C102") (pin "1") (pinfunction "1_1") (pintype "passive"))
      (node (ref "C104") (pin "1") (pinfunction "1_1") (pintype "passive"))
      (node (ref "C105") (pin "1") (pinfunction "1_1") (pintype "passive"))
      (node (ref "C106") (pin "1") (pinfunction "1_1") (pintype "passive"))
      (node (ref "C107") (pin "1") (pinfunction "1_1") (pintype "passive"))
      (node (ref "C108") (pin "1") (pinfunction "1_1") (pintype "passive"))
      (node (ref "C109") (pin "1") (pinfunction "1_1") (pintype "passive"))
      (node (ref "C112") (pin "2") (pinfunction "2_2") (pintype "passive"))
      (node (ref "C113") (pin "2") (pinfunction "2_2") (pintype "passive"))
      (node (ref "C115") (pin "2") (pinfunction "2_2") (pintype "passive"))
      (node (ref "C116") (pin "2") (pinfunction "2_2") (pintype "passive"))
      (node (ref "C117") (pin "2") (pinfunction "2_2") (pintype "passive"))
      (node (ref "C118") (pin "2") (pinfunction "2_2") (pintype "passive"))
      (node (ref "C119") (pin "2") (pinfunction "2_2") (pintype "passive"))
      (node (ref "C120") (pin "1") (pinfunction "1_1") (pintype "passive"))
      (node (ref "C121") (pin "1") (pinfunction "1_1") (pintype "passive"))
      (node (ref "C129") (pin "1") (pinfunction "1_1") (pintype "passive"))
      (node (ref "C130") (pin "1") (pinfunction "1_1") (pintype "passive"))
      (node (ref "C131") (pin "1") (pinfunction "1_1") (pintype "passive"))
      (node (ref "C141") (pin "1") (pinfunction "1_1") (pintype "passive"))
      (node (ref "C58") (pin "1") (pinfunction "1_1") (pintype "passive"))
      (node (ref "C61") (pin "1") (pinfunction "1_1") (pintype "passive"))
      (node (ref "C62") (pin "1") (pinfunction "1_1") (pintype "passive"))
      (node (ref "C86") (pin "1") (pinfunction "1_1") (pintype "passive"))
      (node (ref "C87") (pin "1") (pinfunction "1_1") (pintype "passive"))
      (node (ref "C88") (pin "1") (pinfunction "1_1") (pintype "passive"))
      (node (ref "C89") (pin "1") (pinfunction "1_1") (pintype "passive"))
      (node (ref "C90") (pin "1") (pinfunction "1_1") (pintype "passive"))
      (node (ref "C91") (pin "1") (pinfunction "1_1") (pintype "passive"))
      (node (ref "C92") (pin "1") (pinfunction "1_1") (pintype "passive"))
      (node (ref "C93") (pin "1") (pinfunction "1_1") (pintype "passive"))
      (node (ref "C94") (pin "1") (pinfunction "1_1") (pintype "passive"))
      (node (ref "C95") (pin "1") (pinfunction "1_1") (pintype "passive"))
      (node (ref "C96") (pin "1") (pinfunction "1_1") (pintype "passive"))
      (node (ref "C97") (pin "1") (pinfunction "1_1") (pintype "passive"))
      (node (ref "C98") (pin "1") (pinfunction "1_1") (pintype "passive"))
      (node (ref "C99") (pin "1") (pinfunction "1_1") (pintype "passive"))
      (node (ref "Q5") (pin "2") (pinfunction "S_2") (pintype "passive"))
      (node (ref "R40") (pin "1") (pinfunction "1_1") (pintype "passive"))
      (node (ref "R65") (pin "1") (pinfunction "1_1") (pintype "passive"))
      (node (ref "U2") (pin "A1") (pinfunction "GND_A1") (pintype "power_in"))
      (node (ref "U2") (pin "A11") (pinfunction "GND_A11") (pintype "power_in"))
      (node (ref "U2") (pin "A12") (pinfunction "GND_A12") (pintype "power_in"))
      (node (ref "U2") (pin "A13") (pinfunction "GND_A13") (pintype "power_in"))
      (node (ref "U2") (pin "A14") (pinfunction "GND_A14") (pintype "power_in"))
      (node (ref "U2") (pin "A2") (pinfunction "GND_A2") (pintype "power_in"))
      (node (ref "U2") (pin "A9") (pinfunction "GND_A9") (pintype "power_in"))
      (node (ref "U2") (pin "B1") (pinfunction "GND_B1") (pintype "power_in"))
      (node (ref "U2") (pin "B11") (pinfunction "GND_B11") (pintype "power_in"))
      (node (ref "U2") (pin "B12") (pinfunction "GND_B12") (pintype "power_in"))
      (node (ref "U2") (pin "B2") (pinfunction "GND_B2") (pintype "power_in"))
      (node (ref "U2") (pin "B9") (pinfunction "GND_B9") (pintype "power_in"))
      (node (ref "U2") (pin "C12") (pinfunction "GND_C12") (pintype "power_in"))
      (node (ref "U2") (pin "C13") (pinfunction "GND_C13") (pintype "power_in"))
      (node (ref "U2") (pin "C14") (pinfunction "GND_C14") (pintype "power_in"))
      (node (ref "U2") (pin "C4") (pinfunction "GND_C4") (pintype "power_in"))
      (node (ref "U2") (pin "C5") (pinfunction "GND_C5") (pintype "power_in"))
      (node (ref "U2") (pin "D12") (pinfunction "GND_D12") (pintype "power_in"))
      (node (ref "U2") (pin "D3") (pinfunction "GND_D3") (pintype "power_in"))
      (node (ref "U2") (pin "E12") (pinfunction "GND_E12") (pintype "power_in"))
      (node (ref "U2") (pin "E13") (pinfunction "GND_E13") (pintype "power_in"))
      (node (ref "U2") (pin "E14") (pinfunction "GND_E14") (pintype "power_in"))
      (node (ref "U2") (pin "E3") (pinfunction "GND_E3") (pintype "power_in"))
      (node (ref "U2") (pin "F11") (pinfunction "GND_F11") (pintype "power_in"))
      (node (ref "U2") (pin "F12") (pinfunction "GND_F12") (pintype "power_in"))
      (node (ref "U2") (pin "F3") (pinfunction "GND_F3") (pintype "power_in"))
      (node (ref "U2") (pin "F6") (pinfunction "GND_F6") (pintype "power_in"))
      (node (ref "U2") (pin "F8") (pinfunction "GND_F8") (pintype "power_in"))
      (node (ref "U2") (pin "G1") (pinfunction "GND_G1") (pintype "power_in"))
      (node (ref "U2") (pin "G11") (pinfunction "GND_G11") (pintype "power_in"))
      (node (ref "U2") (pin "G12") (pinfunction "GND_G12") (pintype "power_in"))
      (node (ref "U2") (pin "G13") (pinfunction "GND_G13") (pintype "power_in"))
      (node (ref "U2") (pin "G14") (pinfunction "GND_G14") (pintype "power_in"))
      (node (ref "U2") (pin "G2") (pinfunction "GND_G2") (pintype "power_in"))
      (node (ref "U2") (pin "G3") (pinfunction "GND_G3") (pintype "power_in"))
      (node (ref "U2") (pin "G6") (pinfunction "GND_G6") (pintype "power_in"))
      (node (ref "U2") (pin "G8") (pinfunction "GND_G8") (pintype "power_in"))
      (node (ref "U2") (pin "H11") (pinfunction "GND_H11") (pintype "power_in"))
      (node (ref "U2") (pin "H13") (pinfunction "GND_H13") (pintype "power_in"))
      (node (ref "U2") (pin "H3") (pinfunction "GND_H3") (pintype "power_in"))
      (node (ref "U2") (pin "H6") (pinfunction "GND_H6") (pintype "power_in"))
      (node (ref "U2") (pin "H8") (pinfunction "GND_H8") (pintype "power_in"))
      (node (ref "U2") (pin "J11") (pinfunction "GND_J11") (pintype "power_in"))
      (node (ref "U2") (pin "J13") (pinfunction "GND_J13") (pintype "power_in"))
      (node (ref "U2") (pin "J3") (pinfunction "GND_J3") (pintype "power_in"))
      (node (ref "U2") (pin "J6") (pinfunction "GND_J6") (pintype "power_in"))
      (node (ref "U2") (pin "J8") (pinfunction "GND_J8") (pintype "power_in"))
      (node (ref "U2") (pin "K12") (pinfunction "GND_K12") (pintype "power_in"))
      (node (ref "U2") (pin "K13") (pinfunction "GND_K13") (pintype "power_in"))
      (node (ref "U2") (pin "K14") (pinfunction "GND_K14") (pintype "power_in"))
      (node (ref "U2") (pin "K3") (pinfunction "GND_K3") (pintype "power_in"))
      (node (ref "U2") (pin "L12") (pinfunction "GND_L12") (pintype "power_in"))
      (node (ref "U2") (pin "L3") (pinfunction "GND_L3") (pintype "power_in"))
      (node (ref "U2") (pin "L9") (pinfunction "SCAN_EN_L9") (pintype "input"))
      (node (ref "U2") (pin "M1") (pinfunction "GND_M1") (pintype "power_in"))
      (node (ref "U2") (pin "M12") (pinfunction "GND_M12") (pintype "power_in"))
      (node (ref "U2") (pin "M13") (pinfunction "GND_M13") (pintype "power_in"))
      (node (ref "U2") (pin "M14") (pinfunction "GND_M14") (pintype "power_in"))
      (node (ref "U2") (pin "M2") (pinfunction "GND_M2") (pintype "power_in"))
      (node (ref "U2") (pin "M4") (pinfunction "GND_M4") (pintype "power_in"))
      (node (ref "U2") (pin "N1") (pinfunction "GND_N1") (pintype "power_in"))
      (node (ref "U2") (pin "N10") (pinfunction "GND_N10") (pintype "power_in"))
      (node (ref "U2") (pin "N12") (pinfunction "GND_N12") (pintype "power_in"))
      (node (ref "U2") (pin "N6") (pinfunction "GND_N6") (pintype "power_in"))
      (node (ref "U2") (pin "N8") (pinfunction "GND_N8") (pintype "power_in"))
      (node (ref "U2") (pin "P1") (pinfunction "GND_P1") (pintype "power_in"))
      (node (ref "U2") (pin "P10") (pinfunction "GND_P10") (pintype "power_in"))
      (node (ref "U2") (pin "P12") (pinfunction "GND_P12") (pintype "power_in"))
      (node (ref "U2") (pin "P13") (pinfunction "GND_P13") (pintype "power_in"))
      (node (ref "U2") (pin "P14") (pinfunction "GND_P14") (pintype "power_in"))
      (node (ref "U2") (pin "P6") (pinfunction "GND_P6") (pintype "power_in"))
      (node (ref "U2") (pin "P8") (pinfunction "GND_P8") (pintype "power_in"))
      (node (ref "U6") (pin "13") (pinfunction "GND_13") (pintype "power_in"))
      (node (ref "U6") (pin "17") (pinfunction "GND_17") (pintype "power_in"))
      (node (ref "U7") (pin "4") (pinfunction "GND_4") (pintype "passive"))
      (node (ref "U8") (pin "3") (pinfunction "GND_3") (pintype "power_in"))
    )
    (net (code "116") (name "Net-(C106-Pad2)") (class "Default")
      (node (ref "C106") (pin "2") (pinfunction "2_2") (pintype "passive"))
      (node (ref "C107") (pin "2") (pinfunction "2_2") (pintype "passive"))
      (node (ref "C108") (pin "2") (pinfunction "2_2") (pintype "passive"))
      (node (ref "C109") (pin "2") (pinfunction "2_2") (pintype "passive"))
      (node (ref "L11") (pin "2") (pinfunction "2_2") (pintype "passive"))
      (node (ref "U6") (pin "14") (pinfunction "VCC_14") (pintype "power_in"))
      (node (ref "U6") (pin "7") (pinfunction "VCC_7") (pintype "power_in"))
    )
    (net (code "117") (name "Net-(Q5-D)") (class "Default")
      (node (ref "Q5") (pin "3") (pinfunction "D_3") (pintype "passive"))
      (node (ref "U2") (pin "C6") (pinfunction "RESETN_C6") (pintype "input"))
    )
    (net (code "118") (name "Net-(U2B-CMUFILT0)") (class "Default")
      (node (ref "C116") (pin "1") (pinfunction "1_1") (pintype "passive"))
      (node (ref "U2") (pin "E11") (pinfunction "CMUFILT0_E11") (pintype "passive"))
    )
    (net (code "119") (name "Net-(U2B-CMUFILT1)") (class "Default")
      (node (ref "C117") (pin "1") (pinfunction "1_1") (pintype "passive"))
      (node (ref "U2") (pin "P11") (pinfunction "CMUFILT1_P11") (pintype "passive"))
    )
    (net (code "120") (name "Net-(U2B-CMUFILTER)") (class "Default")
      (node (ref "C115") (pin "1") (pinfunction "1_1") (pintype "passive"))
      (node (ref "U2") (pin "L11") (pinfunction "CMUFILTER_L11") (pintype "passive"))
    )
    (net (code "121") (name "Net-(U2B-RXCRUFILT0)") (class "Default")
      (node (ref "C118") (pin "1") (pinfunction "1_1") (pintype "passive"))
      (node (ref "U2") (pin "C11") (pinfunction "RXCRUFILT0_C11") (pintype "passive"))
    )
    (net (code "122") (name "Net-(U2B-RXCRUFILT1)") (class "Default")
      (node (ref "C119") (pin "1") (pinfunction "1_1") (pintype "passive"))
      (node (ref "U2") (pin "M11") (pinfunction "RXCRUFILT1_M11") (pintype "passive"))
    )
    (net (code "123") (name "Net-(U2B-RXINCM0)") (class "Default")
      (node (ref "C120") (pin "2") (pinfunction "2_2") (pintype "passive"))
      (node (ref "U2") (pin "D11") (pinfunction "RXINCM0_D11") (pintype "passive"))
    )
    (net (code "124") (name "Net-(U2B-RXINCM1)") (class "Default")
      (node (ref "C121") (pin "2") (pinfunction "2_2") (pintype "passive"))
      (node (ref "U2") (pin "N11") (pinfunction "RXINCM1_N11") (pintype "passive"))
    )
    (net (code "125") (name "Net-(U2C-XAUIFILT0)") (class "Default")
      (node (ref "C113") (pin "1") (pinfunction "1_1") (pintype "passive"))
      (node (ref "U2") (pin "C3") (pinfunction "XAUIFILT0_C3") (pintype "passive"))
    )
    (net (code "126") (name "Net-(U2C-XAUIFILT1)") (class "Default")
      (node (ref "C112") (pin "1") (pinfunction "1_1") (pintype "passive"))
      (node (ref "U2") (pin "M3") (pinfunction "XAUIFILT1_M3") (pintype "passive"))
    )
    (net (code "127") (name "Net-(U2D-PADDR1)") (class "Default")
      (node (ref "R60") (pin "1") (pinfunction "1_1") (pintype "passive"))
      (node (ref "U2") (pin "D10") (pinfunction "PADDR1_D10") (pintype "input"))
    )
    (net (code "128") (name "Net-(U2D-PADDR2)") (class "Default")
      (node (ref "R61") (pin "1") (pinfunction "1_1") (pintype "passive"))
      (node (ref "U2") (pin "C8") (pinfunction "PADDR2_C8") (pintype "input"))
    )
    (net (code "129") (name "Net-(U2D-PADDR3)") (class "Default")
      (node (ref "R62") (pin "1") (pinfunction "1_1") (pintype "passive"))
      (node (ref "U2") (pin "E10") (pinfunction "PADDR3_E10") (pintype "input"))
    )
    (net (code "130") (name "Net-(U2D-PADDR4)") (class "Default")
      (node (ref "R63") (pin "1") (pinfunction "1_1") (pintype "passive"))
      (node (ref "U2") (pin "E6") (pinfunction "PADDR4_E6") (pintype "input"))
    )
    (net (code "131") (name "Net-(U2D-STWA0)") (class "Default")
      (node (ref "R57") (pin "1") (pinfunction "1_1") (pintype "passive"))
      (node (ref "U2") (pin "B7") (pinfunction "STWA0_B7") (pintype "input"))
    )
    (net (code "132") (name "Net-(U2D-STWA1)") (class "Default")
      (node (ref "R58") (pin "1") (pinfunction "1_1") (pintype "passive"))
      (node (ref "U2") (pin "A7") (pinfunction "STWA1_A7") (pintype "input"))
    )
    (net (code "133") (name "Net-(U2D-STWA2)") (class "Default")
      (node (ref "R59") (pin "1") (pinfunction "1_1") (pintype "passive"))
      (node (ref "U2") (pin "C10") (pinfunction "STWA2_C10") (pintype "input"))
    )
    (net (code "134") (name "Net-(U2D-TMON)") (class "Default")
      (node (ref "TP20") (pin "1") (pinfunction "1_1") (pintype "passive"))
      (node (ref "U2") (pin "M10") (pinfunction "TMON_M10") (pintype "passive"))
    )
    (net (code "135") (name "Net-(U6-EN)") (class "Default")
      (node (ref "R65") (pin "2") (pinfunction "2_2") (pintype "passive"))
      (node (ref "U6") (pin "8") (pinfunction "EN_8") (pintype "input"))
      (node (ref "U8") (pin "1") (pinfunction "E/D_1") (pintype "input"))
    )
    (net (code "136") (name "Net-(U6-Q2)") (class "Default")
      (node (ref "R69") (pin "2") (pinfunction "2_2") (pintype "passive"))
      (node (ref "U6") (pin "3") (pinfunction "Q2_3") (pintype "output"))
    )
    (net (code "137") (name "Net-(U6-Q2n)") (class "Default")
      (node (ref "R69") (pin "1") (pinfunction "1_1") (pintype "passive"))
      (node (ref "U6") (pin "4") (pinfunction "Q2n_4") (pintype "output"))
    )
    (net (code "138") (name "Net-(U6-Q3)") (class "Default")
      (node (ref "R64") (pin "2") (pinfunction "2_2") (pintype "passive"))
      (node (ref "U6") (pin "5") (pinfunction "Q3_5") (pintype "output"))
    )
    (net (code "139") (name "Net-(U6-Q3n)") (class "Default")
      (node (ref "R64") (pin "1") (pinfunction "1_1") (pintype "passive"))
      (node (ref "U6") (pin "6") (pinfunction "Q3n_6") (pintype "output"))
    )
    (net (code "140") (name "Net-(U7-WP)") (class "Default")
      (node (ref "R40") (pin "2") (pinfunction "2_2") (pintype "passive"))
      (node (ref "U7") (pin "7") (pinfunction "WP_7") (pintype "input"))
    )
    (net (code "141") (name "unconnected-(U2B-RX0CKOUTN-PadA8)") (class "Default")
      (node (ref "U2") (pin "A8") (pinfunction "RX0CKOUTN_A8") (pintype "output+no_connect"))
    )
    (net (code "142") (name "unconnected-(U2B-RX0CKOUTP-PadB8)") (class "Default")
      (node (ref "U2") (pin "B8") (pinfunction "RX0CKOUTP_B8") (pintype "output+no_connect"))
    )
    (net (code "143") (name "unconnected-(U2B-RX1CKOUTN-PadP7)") (class "Default")
      (node (ref "U2") (pin "P7") (pinfunction "RX1CKOUTN_P7") (pintype "output+no_connect"))
    )
    (net (code "144") (name "unconnected-(U2B-RX1CKOUTP-PadN7)") (class "Default")
      (node (ref "U2") (pin "N7") (pinfunction "RX1CKOUTP_N7") (pintype "output+no_connect"))
    )
    (net (code "145") (name "unconnected-(U2B-SREFCKN-PadJ12)") (class "Default")
      (node (ref "U2") (pin "J12") (pinfunction "SREFCKN_J12") (pintype "input+no_connect"))
    )
    (net (code "146") (name "unconnected-(U2B-SREFCKP-PadH12)") (class "Default")
      (node (ref "U2") (pin "H12") (pinfunction "SREFCKP_H12") (pintype "input+no_connect"))
    )
    (net (code "147") (name "unconnected-(U2B-TX0CKOUTN-PadA10)") (class "Default")
      (node (ref "U2") (pin "A10") (pinfunction "TX0CKOUTN_A10") (pintype "output+no_connect"))
    )
    (net (code "148") (name "unconnected-(U2B-TX0CKOUTP-PadB10)") (class "Default")
      (node (ref "U2") (pin "B10") (pinfunction "TX0CKOUTP_B10") (pintype "output+no_connect"))
    )
    (net (code "149") (name "unconnected-(U2B-TX1CKOUTN-PadP9)") (class "Default")
      (node (ref "U2") (pin "P9") (pinfunction "TX1CKOUTN_P9") (pintype "output+no_connect"))
    )
    (net (code "150") (name "unconnected-(U2B-TX1CKOUTP-PadN9)") (class "Default")
      (node (ref "U2") (pin "N9") (pinfunction "TX1CKOUTP_N9") (pintype "output+no_connect"))
    )
    (net (code "151") (name "unconnected-(U2B-WREFCKN-PadJ14)") (class "Default")
      (node (ref "U2") (pin "J14") (pinfunction "WREFCKN_J14") (pintype "input+no_connect"))
    )
    (net (code "152") (name "unconnected-(U2B-WREFCKP-PadH14)") (class "Default")
      (node (ref "U2") (pin "H14") (pinfunction "WREFCKP_H14") (pintype "input+no_connect"))
    )
    (net (code "153") (name "unconnected-(U2D-ANATEST-PadM8)") (class "Default")
      (node (ref "U2") (pin "M8") (pinfunction "ANATEST_M8") (pintype "passive+no_connect"))
    )
    (net (code "154") (name "unconnected-(U2D-GPIO_6-PadK4)") (class "Default")
      (node (ref "U2") (pin "K4") (pinfunction "GPIO_6_K4") (pintype "bidirectional+no_connect"))
    )
    (net (code "155") (name "unconnected-(U2D-GPIO_8-PadK6)") (class "Default")
      (node (ref "U2") (pin "K6") (pinfunction "GPIO_8_K6") (pintype "bidirectional+no_connect"))
    )
    (net (code "156") (name "unconnected-(U2D-RSVD1-PadD8)") (class "Default")
      (node (ref "U2") (pin "D8") (pinfunction "RSVD1_D8") (pintype "passive+no_connect"))
    )
    (net (code "157") (name "unconnected-(U2D-RSVD2-PadE8)") (class "Default")
      (node (ref "U2") (pin "E8") (pinfunction "RSVD2_E8") (pintype "passive+no_connect"))
    )
    (net (code "158") (name "unconnected-(U2D-RSVD3-PadK7)") (class "Default")
      (node (ref "U2") (pin "K7") (pinfunction "RSVD3_K7") (pintype "passive+no_connect"))
    )
    (net (code "159") (name "unconnected-(U2D-RSVD4-PadL7)") (class "Default")
      (node (ref "U2") (pin "L7") (pinfunction "RSVD4_L7") (pintype "passive+no_connect"))
    )
    (net (code "160") (name "unconnected-(U2D-TCK-PadK9)") (class "Default")
      (node (ref "U2") (pin "K9") (pinfunction "TCK_K9") (pintype "input+no_connect"))
    )
    (net (code "161") (name "unconnected-(U2D-TDI-PadL8)") (class "Default")
      (node (ref "U2") (pin "L8") (pinfunction "TDI_L8") (pintype "input+no_connect"))
    )
    (net (code "162") (name "unconnected-(U2D-TDO-PadK8)") (class "Default")
      (node (ref "U2") (pin "K8") (pinfunction "TDO_K8") (pintype "output+no_connect"))
    )
    (net (code "163") (name "unconnected-(U2D-TMS-PadM5)") (class "Default")
      (node (ref "U2") (pin "M5") (pinfunction "TMS_M5") (pintype "input+no_connect"))
    )
    (net (code "164") (name "unconnected-(U6-VREF-AC-Pad10)") (class "Default")
      (node (ref "U6") (pin "10") (pinfunction "VREF-AC_10") (pintype "power_in+no_connect"))
    )
    (net (code "165") (name "unconnected-(U6-VT-Pad11)") (class "Default")
      (node (ref "U6") (pin "11") (pinfunction "VT_11") (pintype "power_in+no_connect"))
    )
    (net (code "166") (name "unconnected-(U7-NC-Pad1)") (class "Default")
      (node (ref "U7") (pin "1") (pinfunction "NC_1") (pintype "passive+no_connect"))
    )
    (net (code "167") (name "unconnected-(U8-NC-Pad2)") (class "Default")
      (node (ref "U8") (pin "2") (pinfunction "NC_2") (pintype "passive+no_connect"))
    )
  )
)
